# MilliNut.net
KiCad netlist of a schematic drawn in Altium Designer
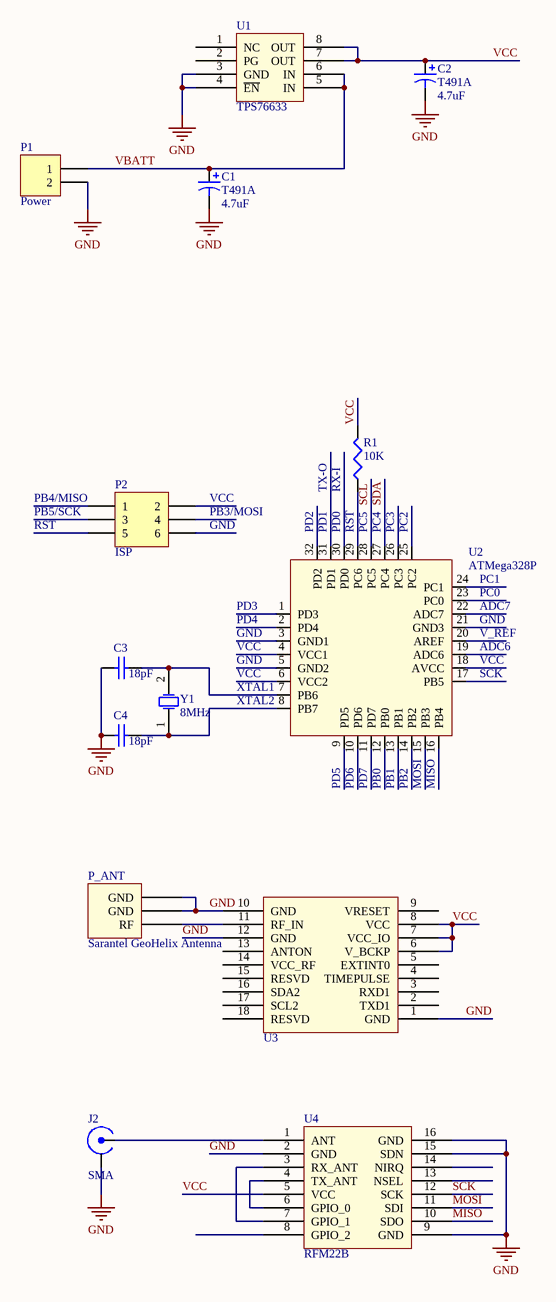
[diagram p0: MilliNut.SchDoc]

(export (version "E")
  (design (tool "Eeschema 10.0.6"))
  (components
    (comp (ref "C1")
      (value "T491A")
      (footprint "A")
      (description "Solid Tantalum Chip Capacitor, Standard T491 Series - Industrial Grade")
      (fields (field (name "ALTIUM_VALUE") "4.7uF") (field (name "PUBLISHER") "Altium Limited"))
      (libsource (lib "KEMET Chip Capacitor") (part "T491A"))
    )
    (comp (ref "C2")
      (value "T491A")
      (footprint "A")
      (description "Solid Tantalum Chip Capacitor, Standard T491 Series - Industrial Grade")
      (fields (field (name "ALTIUM_VALUE") "4.7uF") (field (name "PUBLISHER") "Altium Limited"))
      (libsource (lib "KEMET Chip Capacitor") (part "T491A"))
    )
    (comp (ref "C3")
      (value "18pF")
      (footprint "1608[0603]")
      (description "Ceramic Chip Capacitor - Standard")
      (fields (field (name "Comment") "C0805") (field (name "PUBLISHER") "Altium Limited"))
      (libsource (lib "KEMET Chip Capacitor") (part "C0805"))
    )
    (comp (ref "C4")
      (value "18pF")
      (footprint "1608[0603]")
      (description "Ceramic Chip Capacitor - Standard")
      (fields (field (name "Comment") "C0805") (field (name "PUBLISHER") "Altium Limited"))
      (libsource (lib "KEMET Chip Capacitor") (part "C0805"))
    )
    (comp (ref "J2")
      (value "SMA")
      (footprint "Darkside_Lib:CON SMA PCB 90")
      (description "Power Connector")
      (fields (field (name "Comment") "SMA_L"))
      (libsource (lib "Darkside_Lib") (part "SMA_L"))
    )
    (comp (ref "P1")
      (value "Power")
      (footprint "HDR1X2")
      (description "Header, 2-Pin")
      (fields (field (name "PUBLISHER") "Altium Limited"))
      (libsource (lib "Miscellaneous Connectors") (part "Header 2"))
    )
    (comp (ref "P2")
      (value "ISP")
      (footprint "HDR2X3")
      (description "Header, 3-Pin, Dual row")
      (fields (field (name "PUBLISHER") "Altium Limited"))
      (libsource (lib "Miscellaneous Connectors") (part "Header 3X2"))
    )
    (comp (ref "P_ANT")
      (value "Sarantel GeoHelix Antenna")
      (footprint "Darkside_Lib:Sarantel SL1202RH")
      (libsource (lib "Darkside_Lib") (part "Sarantel GeoHelix Antenna"))
    )
    (comp (ref "R1")
      (value "10K")
      (footprint "1608[0603]")
      (description "Resistor")
      (fields (field (name "Comment") "Res3") (field (name "PUBLISHER") "Altium Limited"))
      (libsource (lib "Miscellaneous Devices") (part "Res3"))
    )
    (comp (ref "U1")
      (value "TPS76633")
      (footprint "TPS76633")
      (libsource (lib "Darkside_Lib") (part "TPS76633"))
    )
    (comp (ref "U2")
      (value "ATMega328P")
      (footprint "Darkside_Lib:TQFP32")
      (libsource (lib "Darkside_Lib") (part "ATMega328P"))
    )
    (comp (ref "U3")
      (value "uBlox MAX-6Q")
      (footprint "MAX-6Q")
      (libsource (lib "Darkside_Lib") (part "uBlox MAX-6Q"))
    )
    (comp (ref "U4")
      (value "RFM22B")
      (footprint "RFM22B")
      (libsource (lib "Darkside_Lib") (part "RFM22B-S2"))
    )
    (comp (ref "Y1")
      (value "8MHz")
      (footprint "ABM3_XTAL")
      (description "Crystal Oscillator")
      (fields (field (name "PUBLISHER") "Altium Limited"))
      (libsource (lib "ECS Crystal Oscillator") (part "ECS-110-S-1"))
    )
  )
  (nets
    (net (code "1") (name "/ADC6") (class "Default")
      (node (ref "U2") (pin "19") (pinfunction "ADC6_19") (pintype "passive"))
    )
    (net (code "2") (name "/ADC7") (class "Default")
      (node (ref "U2") (pin "22") (pinfunction "ADC7_22") (pintype "passive"))
    )
    (net (code "3") (name "/MISO") (class "Default")
      (node (ref "U2") (pin "16") (pinfunction "PB4_16") (pintype "passive"))
      (node (ref "U4") (pin "10") (pinfunction "SDO_10") (pintype "passive"))
    )
    (net (code "4") (name "/MOSI") (class "Default")
      (node (ref "U2") (pin "15") (pinfunction "PB3_15") (pintype "passive"))
      (node (ref "U4") (pin "11") (pinfunction "SDI_11") (pintype "passive"))
    )
    (net (code "5") (name "/PB0") (class "Default")
      (node (ref "U2") (pin "12") (pinfunction "PB0_12") (pintype "passive"))
    )
    (net (code "6") (name "/PB1") (class "Default")
      (node (ref "U2") (pin "13") (pinfunction "PB1_13") (pintype "passive"))
    )
    (net (code "7") (name "/PB2") (class "Default")
      (node (ref "U2") (pin "14") (pinfunction "PB2_14") (pintype "passive"))
    )
    (net (code "8") (name "/PB3{slash}MOSI") (class "Default")
      (node (ref "P2") (pin "4") (pinfunction "4_4") (pintype "passive"))
    )
    (net (code "9") (name "/PB4{slash}MISO") (class "Default")
      (node (ref "P2") (pin "1") (pinfunction "1_1") (pintype "passive"))
    )
    (net (code "10") (name "/PB5{slash}SCK") (class "Default")
      (node (ref "P2") (pin "3") (pinfunction "3_3") (pintype "passive"))
    )
    (net (code "11") (name "/PC0") (class "Default")
      (node (ref "U2") (pin "23") (pinfunction "PC0_23") (pintype "passive"))
    )
    (net (code "12") (name "/PC1") (class "Default")
      (node (ref "U2") (pin "24") (pinfunction "PC1_24") (pintype "passive"))
    )
    (net (code "13") (name "/PC2") (class "Default")
      (node (ref "U2") (pin "25") (pinfunction "PC2_25") (pintype "passive"))
    )
    (net (code "14") (name "/PC3") (class "Default")
      (node (ref "U2") (pin "26") (pinfunction "PC3_26") (pintype "passive"))
    )
    (net (code "15") (name "/PC4") (class "Default")
      (node (ref "U2") (pin "27") (pinfunction "PC4_27") (pintype "passive"))
    )
    (net (code "16") (name "/PC5") (class "Default")
      (node (ref "U2") (pin "28") (pinfunction "PC5_28") (pintype "passive"))
    )
    (net (code "17") (name "/PD0") (class "Default")
      (node (ref "U2") (pin "30") (pinfunction "PD0_30") (pintype "passive"))
    )
    (net (code "18") (name "/PD1") (class "Default")
      (node (ref "U2") (pin "31") (pinfunction "PD1_31") (pintype "passive"))
    )
    (net (code "19") (name "/PD2") (class "Default")
      (node (ref "U2") (pin "32") (pinfunction "PD2_32") (pintype "passive"))
    )
    (net (code "20") (name "/PD3") (class "Default")
      (node (ref "U2") (pin "1") (pinfunction "PD3_1") (pintype "passive"))
    )
    (net (code "21") (name "/PD4") (class "Default")
      (node (ref "U2") (pin "2") (pinfunction "PD4_2") (pintype "passive"))
    )
    (net (code "22") (name "/PD5") (class "Default")
      (node (ref "U2") (pin "9") (pinfunction "PD5_9") (pintype "passive"))
    )
    (net (code "23") (name "/PD6") (class "Default")
      (node (ref "U2") (pin "10") (pinfunction "PD6_10") (pintype "passive"))
    )
    (net (code "24") (name "/PD7") (class "Default")
      (node (ref "U2") (pin "11") (pinfunction "PD7_11") (pintype "passive"))
    )
    (net (code "25") (name "/RST") (class "Default")
      (node (ref "P2") (pin "5") (pinfunction "5_5") (pintype "passive"))
      (node (ref "R1") (pin "1") (pinfunction "1_1") (pintype "passive"))
      (node (ref "U2") (pin "29") (pinfunction "PC6_29") (pintype "passive"))
    )
    (net (code "26") (name "/SCK") (class "Default")
      (node (ref "U2") (pin "17") (pinfunction "PB5_17") (pintype "passive"))
      (node (ref "U4") (pin "12") (pinfunction "SCK_12") (pintype "passive"))
    )
    (net (code "27") (name "/VBATT") (class "Default")
      (node (ref "C1") (pin "1") (pinfunction "1_1") (pintype "passive"))
      (node (ref "P1") (pin "1") (pinfunction "1_1") (pintype "passive"))
      (node (ref "U1") (pin "5") (pinfunction "IN_5") (pintype "passive"))
      (node (ref "U1") (pin "6") (pinfunction "IN_6") (pintype "passive"))
    )
    (net (code "28") (name "/VCC") (class "Default")
      (node (ref "C2") (pin "1") (pinfunction "1_1") (pintype "passive"))
      (node (ref "P2") (pin "2") (pinfunction "2_2") (pintype "passive"))
      (node (ref "R1") (pin "2") (pinfunction "2_2") (pintype "passive"))
      (node (ref "U1") (pin "7") (pinfunction "OUT_7") (pintype "passive"))
      (node (ref "U1") (pin "8") (pinfunction "OUT_8") (pintype "passive"))
      (node (ref "U2") (pin "18") (pinfunction "AVCC_18") (pintype "passive"))
      (node (ref "U2") (pin "4") (pinfunction "VCC1_4") (pintype "passive"))
      (node (ref "U2") (pin "6") (pinfunction "VCC2_6") (pintype "passive"))
      (node (ref "U3") (pin "6") (pinfunction "V_BCKP_6") (pintype "passive"))
      (node (ref "U3") (pin "7") (pinfunction "VCC_IO_7") (pintype "passive"))
      (node (ref "U3") (pin "8") (pinfunction "VCC_8") (pintype "passive"))
      (node (ref "U4") (pin "5") (pinfunction "VCC_5") (pintype "passive"))
    )
    (net (code "29") (name "/V_REF") (class "Default")
      (node (ref "U2") (pin "20") (pinfunction "AREF_20") (pintype "passive"))
    )
    (net (code "30") (name "/XTAL1") (class "Default")
      (node (ref "C3") (pin "2") (pinfunction "2_2") (pintype "passive"))
      (node (ref "U2") (pin "7") (pinfunction "PB6_7") (pintype "passive"))
      (node (ref "Y1") (pin "2") (pinfunction "OSC2_2") (pintype "passive"))
    )
    (net (code "31") (name "/XTAL2") (class "Default")
      (node (ref "C4") (pin "2") (pinfunction "2_2") (pintype "passive"))
      (node (ref "U2") (pin "8") (pinfunction "PB7_8") (pintype "passive"))
      (node (ref "Y1") (pin "1") (pinfunction "OSC1_1") (pintype "passive"))
    )
    (net (code "32") (name "GND") (class "Default")
      (node (ref "C1") (pin "2") (pinfunction "2_2") (pintype "passive"))
      (node (ref "C2") (pin "2") (pinfunction "2_2") (pintype "passive"))
      (node (ref "C3") (pin "1") (pinfunction "1_1") (pintype "passive"))
      (node (ref "C4") (pin "1") (pinfunction "1_1") (pintype "passive"))
      (node (ref "J2") (pin "2") (pinfunction "2_2") (pintype "passive"))
      (node (ref "P1") (pin "2") (pinfunction "2_2") (pintype "passive"))
      (node (ref "P2") (pin "6") (pinfunction "6_6") (pintype "passive"))
      (node (ref "P_ANT") (pin "2") (pinfunction "GND_2") (pintype "passive"))
      (node (ref "P_ANT") (pin "3") (pinfunction "GND_3") (pintype "passive"))
      (node (ref "U1") (pin "3") (pinfunction "GND_3") (pintype "passive"))
      (node (ref "U1") (pin "4") (pinfunction "~{EN}_4") (pintype "passive"))
      (node (ref "U2") (pin "21") (pinfunction "GND3_21") (pintype "passive"))
      (node (ref "U2") (pin "3") (pinfunction "GND1_3") (pintype "passive"))
      (node (ref "U2") (pin "5") (pinfunction "GND2_5") (pintype "passive"))
      (node (ref "U3") (pin "1") (pinfunction "GND_1") (pintype "passive"))
      (node (ref "U3") (pin "10") (pinfunction "GND_10") (pintype "passive"))
      (node (ref "U3") (pin "12") (pinfunction "GND_12") (pintype "passive"))
      (node (ref "U4") (pin "15") (pinfunction "SDN_15") (pintype "passive"))
      (node (ref "U4") (pin "16") (pinfunction "GND_16") (pintype "passive"))
      (node (ref "U4") (pin "2") (pinfunction "GND_2") (pintype "passive"))
      (node (ref "U4") (pin "9") (pinfunction "GND_9") (pintype "passive"))
    )
    (net (code "33") (name "Net-(P_ANT-RF)") (class "Default")
      (node (ref "P_ANT") (pin "1") (pinfunction "RF_1") (pintype "passive"))
      (node (ref "U3") (pin "11") (pinfunction "RF_IN_11") (pintype "passive"))
    )
    (net (code "34") (name "Net-(U4-ANT)") (class "Default")
      (node (ref "J2") (pin "1") (pinfunction "1_1") (pintype "passive"))
      (node (ref "U4") (pin "1") (pinfunction "ANT_1") (pintype "passive"))
    )
    (net (code "35") (name "Net-(U4-GPIO_0)") (class "Default")
      (node (ref "U4") (pin "4") (pinfunction "TX_ANT_4") (pintype "passive"))
      (node (ref "U4") (pin "6") (pinfunction "GPIO_0_6") (pintype "passive"))
    )
    (net (code "36") (name "Net-(U4-GPIO_1)") (class "Default")
      (node (ref "U4") (pin "3") (pinfunction "RX_ANT_3") (pintype "passive"))
      (node (ref "U4") (pin "7") (pinfunction "GPIO_1_7") (pintype "passive"))
    )
    (net (code "37") (name "unconnected-(U1-NC-Pad1)") (class "Default")
      (node (ref "U1") (pin "1") (pinfunction "NC_1") (pintype "passive"))
    )
    (net (code "38") (name "unconnected-(U1-PG-Pad2)") (class "Default")
      (node (ref "U1") (pin "2") (pinfunction "PG_2") (pintype "passive"))
    )
    (net (code "39") (name "unconnected-(U3-ANTON-Pad13)") (class "Default")
      (node (ref "U3") (pin "13") (pinfunction "ANTON_13") (pintype "passive"))
    )
    (net (code "40") (name "unconnected-(U3-EXTINT0-Pad5)") (class "Default")
      (node (ref "U3") (pin "5") (pinfunction "EXTINT0_5") (pintype "passive"))
    )
    (net (code "41") (name "unconnected-(U3-RESVD-Pad15)") (class "Default")
      (node (ref "U3") (pin "15") (pinfunction "RESVD_15") (pintype "passive"))
    )
    (net (code "42") (name "unconnected-(U3-RESVD-Pad18)") (class "Default")
      (node (ref "U3") (pin "18") (pinfunction "RESVD_18") (pintype "passive"))
    )
    (net (code "43") (name "unconnected-(U3-RXD1-Pad3)") (class "Default")
      (node (ref "U3") (pin "3") (pinfunction "RXD1_3") (pintype "passive"))
    )
    (net (code "44") (name "unconnected-(U3-SCL2-Pad17)") (class "Default")
      (node (ref "U3") (pin "17") (pinfunction "SCL2_17") (pintype "passive"))
    )
    (net (code "45") (name "unconnected-(U3-SDA2-Pad16)") (class "Default")
      (node (ref "U3") (pin "16") (pinfunction "SDA2_16") (pintype "passive"))
    )
    (net (code "46") (name "unconnected-(U3-TIMEPULSE-Pad4)") (class "Default")
      (node (ref "U3") (pin "4") (pinfunction "TIMEPULSE_4") (pintype "passive"))
    )
    (net (code "47") (name "unconnected-(U3-TXD1-Pad2)") (class "Default")
      (node (ref "U3") (pin "2") (pinfunction "TXD1_2") (pintype "passive"))
    )
    (net (code "48") (name "unconnected-(U3-VCC_RF-Pad14)") (class "Default")
      (node (ref "U3") (pin "14") (pinfunction "VCC_RF_14") (pintype "passive"))
    )
    (net (code "49") (name "unconnected-(U3-VRESET-Pad9)") (class "Default")
      (node (ref "U3") (pin "9") (pinfunction "VRESET_9") (pintype "passive"))
    )
    (net (code "50") (name "unconnected-(U4-GPIO_2-Pad8)") (class "Default")
      (node (ref "U4") (pin "8") (pinfunction "GPIO_2_8") (pintype "passive"))
    )
    (net (code "51") (name "unconnected-(U4-NIRQ-Pad14)") (class "Default")
      (node (ref "U4") (pin "14") (pinfunction "NIRQ_14") (pintype "passive"))
    )
    (net (code "52") (name "unconnected-(U4-NSEL-Pad13)") (class "Default")
      (node (ref "U4") (pin "13") (pinfunction "NSEL_13") (pintype "passive"))
    )
  )
)
